# Regulador.net
KiCad netlist of a schematic drawn in Altium Designer
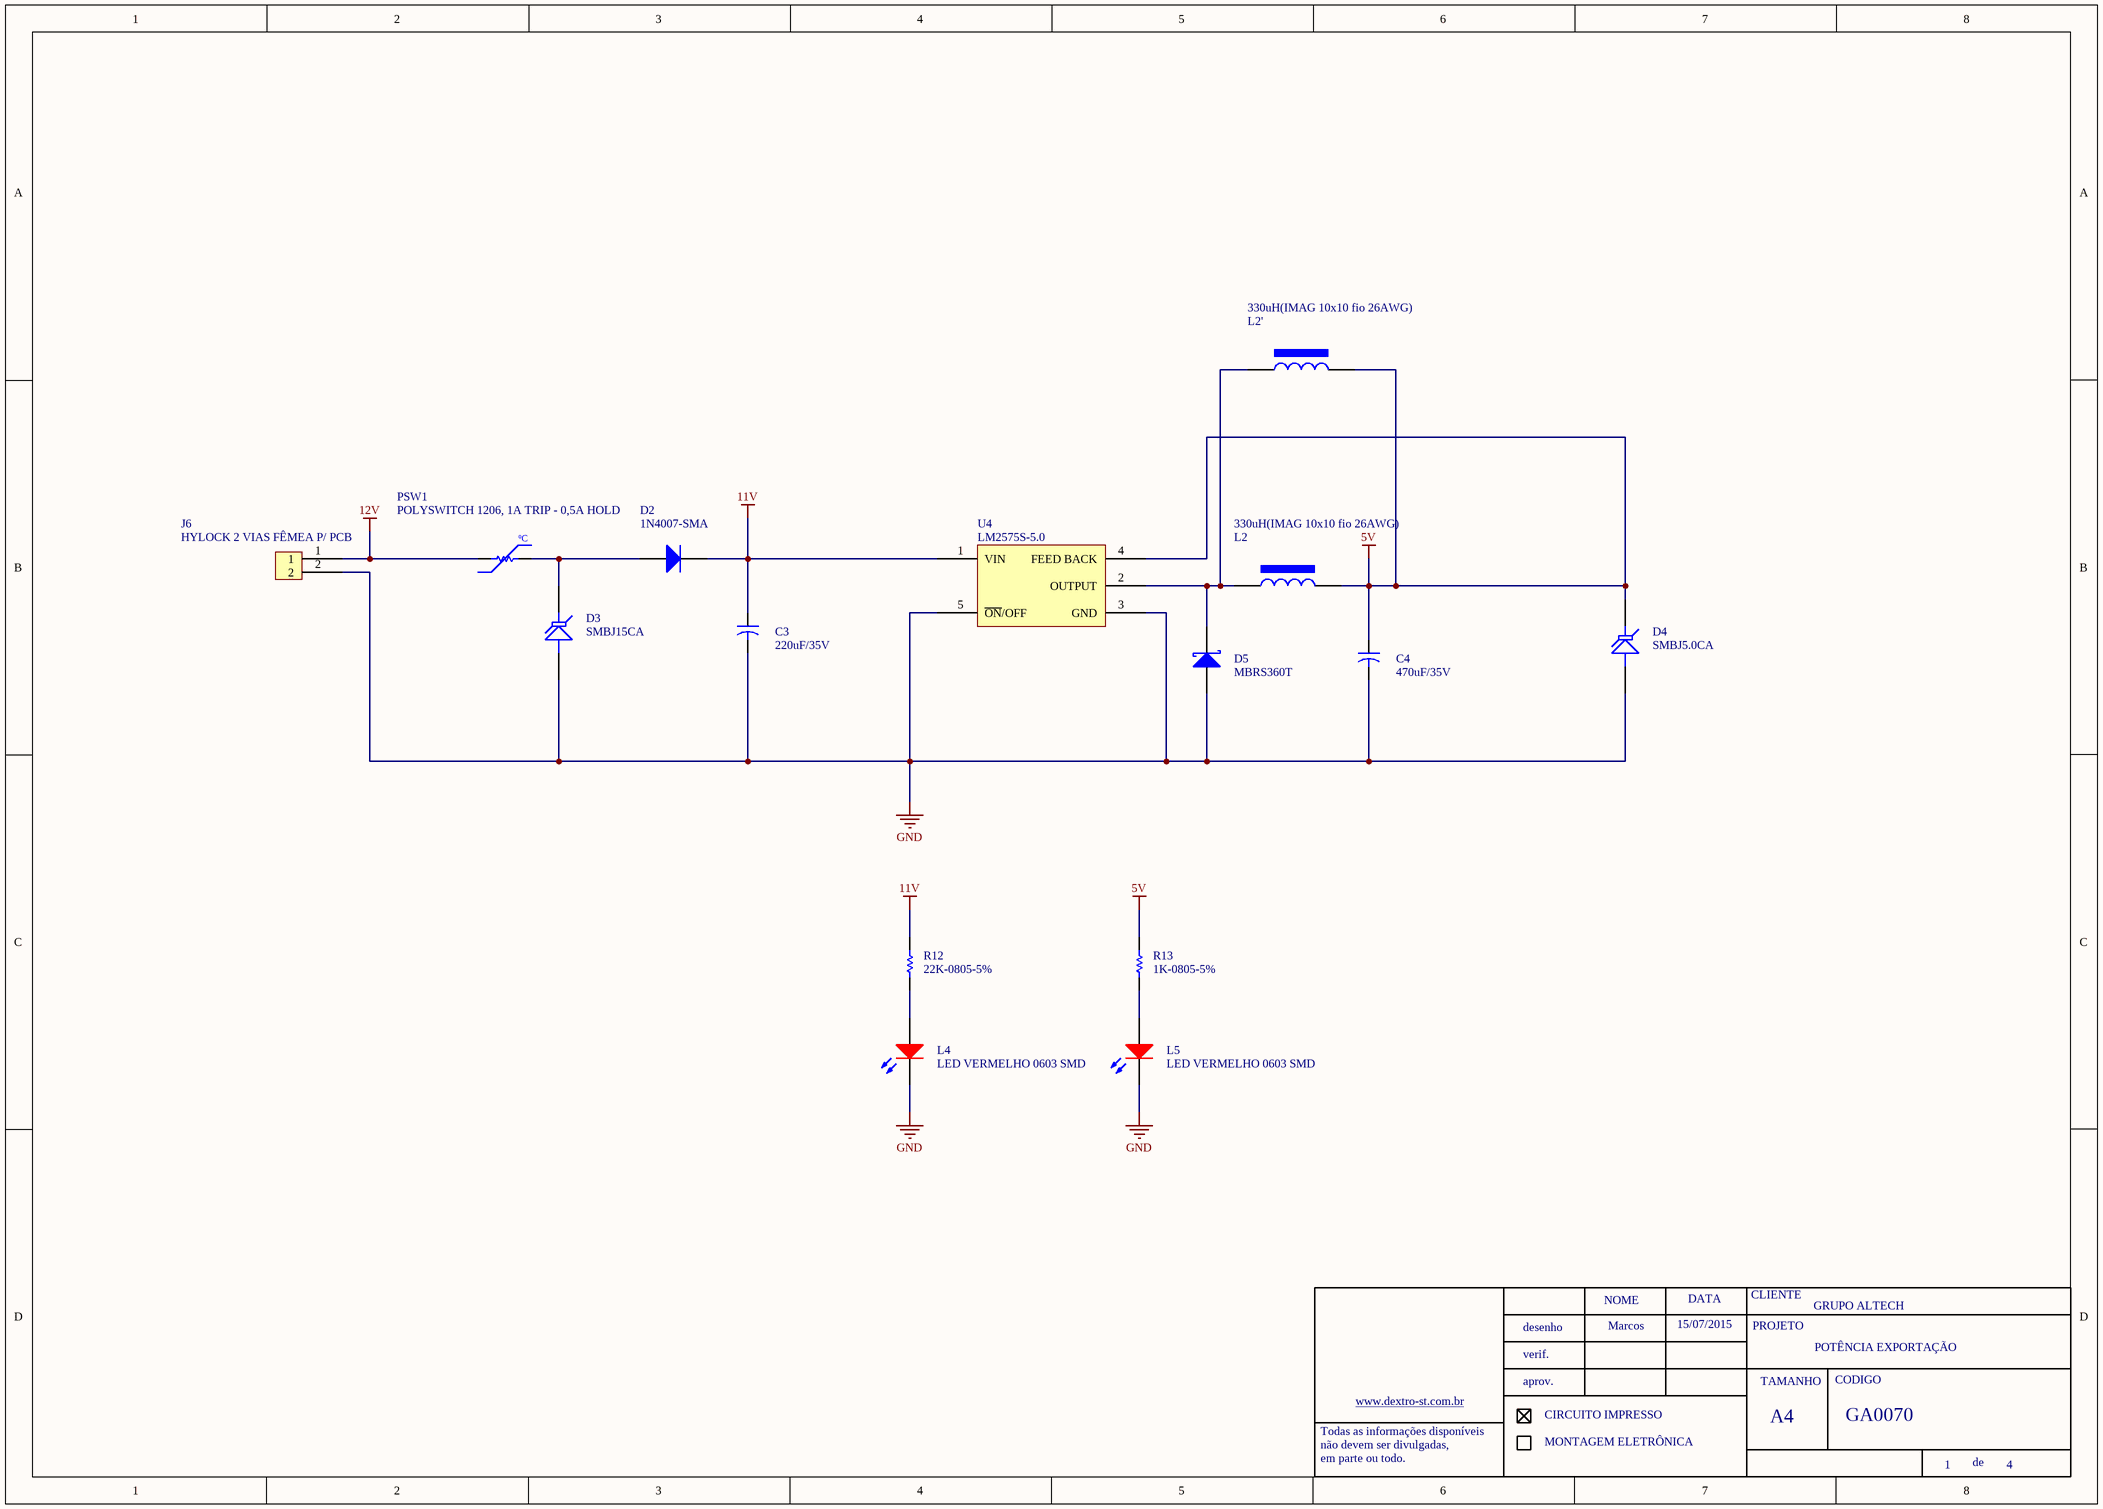
[diagram p0: Regulador.SchDoc]

(export (version "E")
  (design (tool "Eeschema 10.0.6"))
  (components
    (comp (ref "C3")
      (value "220uF/35V")
      (footprint "CAP POL 8x12mm")
      (description "2200uF/50V")
      (libsource (lib "AquinoLib") (part "2200uF/50V"))
    )
    (comp (ref "C4")
      (value "470uF/35V")
      (footprint "CAP POL 8x12mm")
      (description "470uF/50V")
      (libsource (lib "AquinoLib") (part "470uF/50V"))
    )
    (comp (ref "D2")
      (value "1N4007-SMA")
      (footprint "DO-214AA")
      (description "1N4007")
      (libsource (lib "AquinoLib") (part "1N4007"))
    )
    (comp (ref "D3")
      (value "SMBJ15CA")
      (footprint "DO-214AA")
      (description "SMBJ30.0A")
      (libsource (lib "AquinoLib") (part "SMBJ30.0A"))
    )
    (comp (ref "D4")
      (value "SMBJ5.0CA")
      (footprint "DO-214AA")
      (description "SMBJ5.0A")
      (libsource (lib "AquinoLib") (part "SMBJ5.0A"))
    )
    (comp (ref "D5")
      (value "MBRS360T")
      (footprint "DO-214AA")
      (description "1N5819-SOD80")
      (libsource (lib "AquinoLib") (part "1N5819-SOD80"))
    )
    (comp (ref "J6")
      (value "HYLOCK 2 VIAS FÊMEA P/ PCB")
      (footprint "CONECTOR HYLOCK 2 VIAS")
      (description "PCMC2-2")
      (libsource (lib "AquinoLib") (part "PCMC2-2"))
    )
    (comp (ref "L2")
      (value "330uH(IMAG 10x10 fio 26AWG)")
      (footprint "INDUTOR 47mH")
      (description "1mH-CNF15-26 AWG")
      (libsource (lib "AquinoLib") (part "indutor 1mH CNF15"))
    )
    (comp (ref "L2'")
      (value "330uH(IMAG 10x10 fio 26AWG)")
      (footprint "INDUTOR LOCO")
      (description "1mH-CNF15-26 AWG")
      (libsource (lib "AquinoLib") (part "indutor 1mH CNF15"))
    )
    (comp (ref "L4")
      (value "LED VERMELHO 0603 SMD")
      (footprint "LED 1206")
      (libsource (lib "AquinoLib") (part "LED VERMELHO 0603 SMD"))
    )
    (comp (ref "L5")
      (value "LED VERMELHO 0603 SMD")
      (footprint "LED 1206")
      (libsource (lib "AquinoLib") (part "LED VERMELHO 0603 SMD"))
    )
    (comp (ref "PSW1")
      (value "POLYSWITCH 1206, 1A TRIP - 0,5A HOLD")
      (footprint "1206-REVISADO ONDA")
      (description "NANOSMDC020F-2")
      (libsource (lib "AquinoLib") (part "POLYSWITCH 200mA"))
    )
    (comp (ref "R12")
      (value "22K-0805-5%")
      (footprint "0805-REVISADO ONDA")
      (libsource (lib "AquinoLib") (part "22K-0805-5%"))
    )
    (comp (ref "R13")
      (value "1K-0805-5%")
      (footprint "0805-REVISADO ONDA")
      (description "22K-0805-5%")
      (libsource (lib "AquinoLib") (part "22K-0805-5%"))
    )
    (comp (ref "U4")
      (value "LM2575S-5.0")
      (footprint "TO-263-5")
      (description "LM2596S-ADJ")
      (libsource (lib "AquinoLib") (part "LM2596S-ADJ"))
    )
  )
  (nets
    (net (code "1") (name "5V") (class "Default")
      (node (ref "C4") (pin "1") (pinfunction "1_1") (pintype "passive"))
      (node (ref "D4") (pin "2") (pinfunction "K_2") (pintype "passive"))
      (node (ref "L2") (pin "1") (pinfunction "1_1") (pintype "passive"))
      (node (ref "L2'") (pin "1") (pinfunction "1_1") (pintype "passive"))
      (node (ref "R13") (pin "2") (pinfunction "2_2") (pintype "passive"))
      (node (ref "U4") (pin "4") (pinfunction "FEED_BACK_4") (pintype "passive"))
    )
    (net (code "2") (name "11V") (class "Default")
      (node (ref "C3") (pin "1") (pinfunction "1_1") (pintype "passive"))
      (node (ref "D2") (pin "2") (pinfunction "K_2") (pintype "passive"))
      (node (ref "R12") (pin "2") (pinfunction "2_2") (pintype "passive"))
      (node (ref "U4") (pin "1") (pinfunction "VIN_1") (pintype "passive"))
    )
    (net (code "3") (name "12V") (class "Default")
      (node (ref "J6") (pin "1") (pinfunction "1_1") (pintype "passive"))
      (node (ref "PSW1") (pin "1") (pinfunction "1_1") (pintype "passive"))
    )
    (net (code "4") (name "GND") (class "Default")
      (node (ref "C3") (pin "2") (pinfunction "2_2") (pintype "passive"))
      (node (ref "C4") (pin "2") (pinfunction "2_2") (pintype "passive"))
      (node (ref "D3") (pin "1") (pinfunction "A_1") (pintype "passive"))
      (node (ref "D4") (pin "1") (pinfunction "A_1") (pintype "passive"))
      (node (ref "D5") (pin "1") (pinfunction "A_1") (pintype "passive"))
      (node (ref "J6") (pin "2") (pinfunction "2_2") (pintype "passive"))
      (node (ref "L4") (pin "2") (pinfunction "K_2") (pintype "passive"))
      (node (ref "L5") (pin "2") (pinfunction "K_2") (pintype "passive"))
      (node (ref "U4") (pin "3") (pinfunction "GND_3") (pintype "passive"))
      (node (ref "U4") (pin "5") (pinfunction "~{ON}/OFF_5") (pintype "passive"))
    )
    (net (code "5") (name "Net-(D2-A)") (class "Default")
      (node (ref "D2") (pin "1") (pinfunction "A_1") (pintype "passive"))
      (node (ref "D3") (pin "2") (pinfunction "K_2") (pintype "passive"))
      (node (ref "PSW1") (pin "2") (pinfunction "2_2") (pintype "passive"))
    )
    (net (code "6") (name "Net-(D5-K)") (class "Default")
      (node (ref "D5") (pin "2") (pinfunction "K_2") (pintype "passive"))
      (node (ref "L2") (pin "2") (pinfunction "2_2") (pintype "passive"))
      (node (ref "L2'") (pin "2") (pinfunction "2_2") (pintype "passive"))
      (node (ref "U4") (pin "2") (pinfunction "OUTPUT_2") (pintype "passive"))
    )
    (net (code "7") (name "Net-(L4-A)") (class "Default")
      (node (ref "L4") (pin "1") (pinfunction "A_1") (pintype "passive"))
      (node (ref "R12") (pin "1") (pinfunction "1_1") (pintype "passive"))
    )
    (net (code "8") (name "Net-(L5-A)") (class "Default")
      (node (ref "L5") (pin "1") (pinfunction "A_1") (pintype "passive"))
      (node (ref "R13") (pin "1") (pinfunction "1_1") (pintype "passive"))
    )
  )
)
